# T06_preliminarySchematic_v4.net
KiCad netlist of a schematic drawn in EAGLE
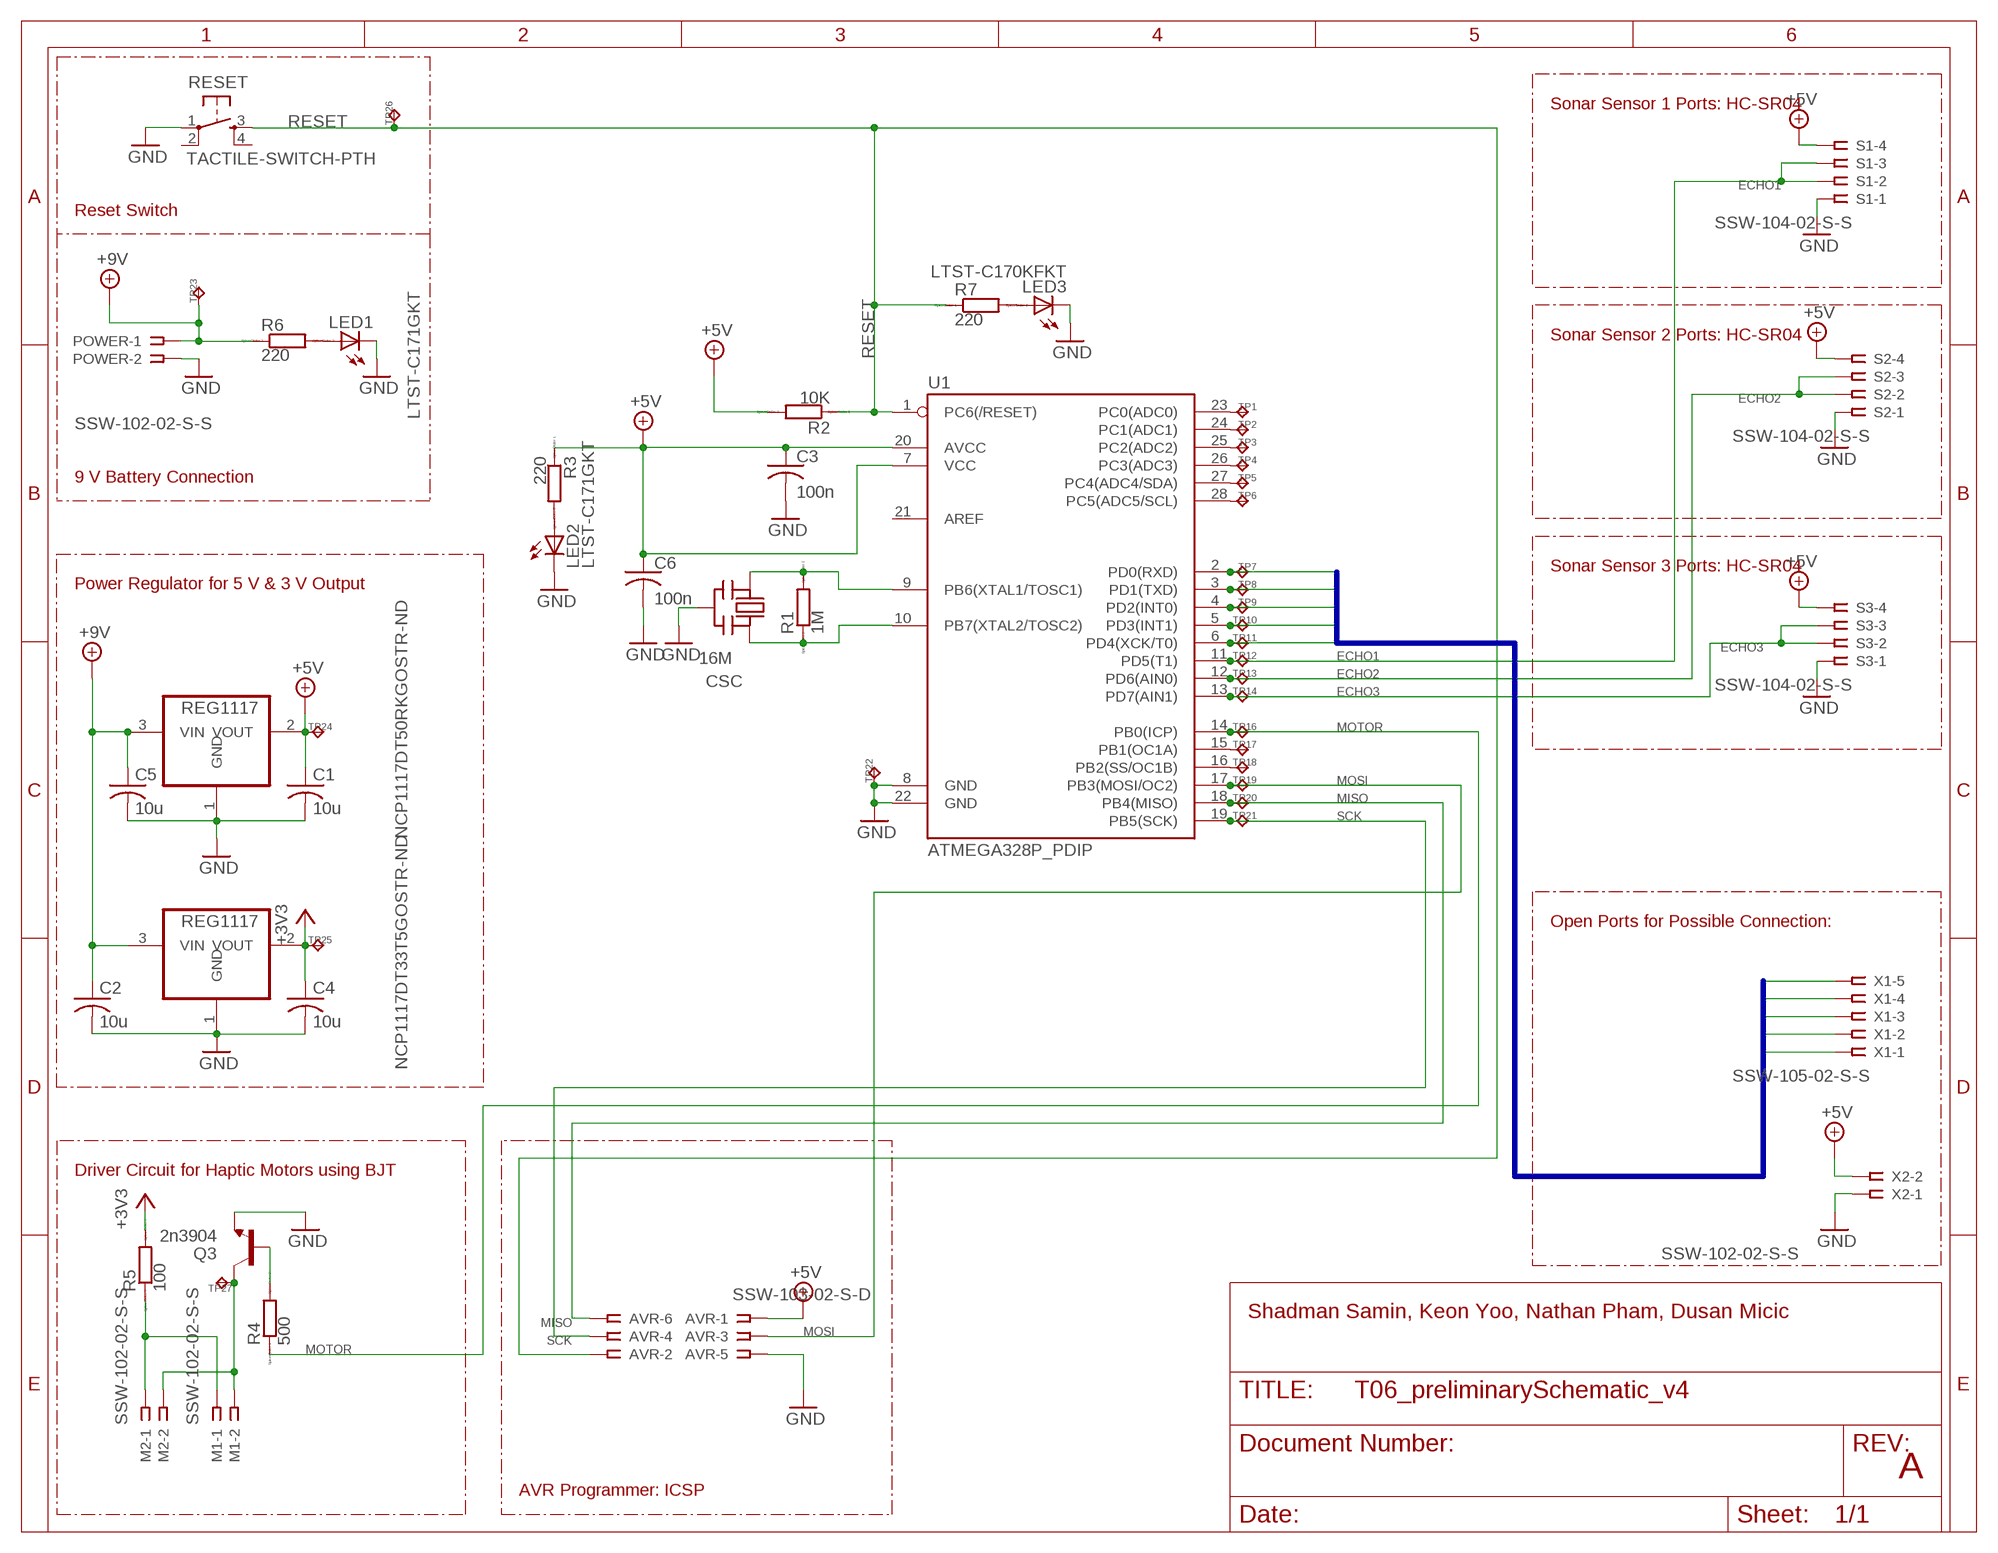
[diagram p0: schematic, sheet 1]

(export (version "E")
  (design (tool "Eeschema 10.0.6"))
  (components
    (comp (ref "AVR")
      (value "SSW-103-02-S-D")
      (footprint "eagle-import:SSW-103-02-S-D")
      (libsource (lib "eagle-import") (part "SSW-103-02-S-D"))
    )
    (comp (ref "C1")
      (value "10u")
      (footprint "eagle-import:C0805K")
      (libsource (lib "eagle-import") (part "C-USC0805K"))
    )
    (comp (ref "C2")
      (value "10u")
      (footprint "eagle-import:C0805K")
      (libsource (lib "eagle-import") (part "C-USC0805K"))
    )
    (comp (ref "C3")
      (value "100n")
      (footprint "eagle-import:C0805K")
      (libsource (lib "eagle-import") (part "rcl_C-USC0805K"))
    )
    (comp (ref "C4")
      (value "10u")
      (footprint "eagle-import:C0805K")
      (libsource (lib "eagle-import") (part "C-USC0805K"))
    )
    (comp (ref "C5")
      (value "10u")
      (footprint "eagle-import:C0805K")
      (libsource (lib "eagle-import") (part "C-USC0805K"))
    )
    (comp (ref "C6")
      (value "100n")
      (footprint "eagle-import:C0805K")
      (libsource (lib "eagle-import") (part "rcl_C-USC0805K"))
    )
    (comp (ref "CSC")
      (value "16M")
      (footprint "eagle-import:CSTCR-G")
      (libsource (lib "eagle-import") (part "CERMOSCILL-CSTCRG"))
    )
    (comp (ref "LED1")
      (value "LTST-C171GKT")
      (footprint "eagle-import:CHIPLED_0805")
      (libsource (lib "eagle-import") (part "LEDCHIPLED_0805"))
    )
    (comp (ref "LED2")
      (value "LTST-C171GKT")
      (footprint "eagle-import:CHIP-LED0805")
      (libsource (lib "eagle-import") (part "LEDCHIP-LED0805"))
    )
    (comp (ref "LED3")
      (value "LTST-C170KFKT")
      (footprint "eagle-import:CHIP-LED0805")
      (libsource (lib "eagle-import") (part "LEDCHIP-LED0805"))
    )
    (comp (ref "M1")
      (value "SSW-102-02-S-S")
      (footprint "eagle-import:SSW-102-02-S-S")
      (libsource (lib "eagle-import") (part "SSW-102-02-S-S"))
    )
    (comp (ref "M2")
      (value "SSW-102-02-S-S")
      (footprint "eagle-import:SSW-102-02-S-S")
      (libsource (lib "eagle-import") (part "SSW-102-02-S-S"))
    )
    (comp (ref "NCP1117DT33T5GOSTR-ND")
      (value "REG1117")
      (footprint "eagle-import:SOT223")
      (libsource (lib "eagle-import") (part "REG1117"))
    )
    (comp (ref "NCP1117DT50RKGOSTR-ND")
      (value "REG1117")
      (footprint "eagle-import:SOT223")
      (libsource (lib "eagle-import") (part "REG1117"))
    )
    (comp (ref "POWER")
      (value "SSW-102-02-S-S")
      (footprint "eagle-import:SSW-102-02-S-S")
      (libsource (lib "eagle-import") (part "SSW-102-02-S-S"))
    )
    (comp (ref "Q3")
      (value "2n3904")
      (footprint "eagle-import:TO-92")
      (libsource (lib "eagle-import") (part "TRANSISTOR_NPN2N3904"))
    )
    (comp (ref "R1")
      (value "1M")
      (footprint "eagle-import:R0603")
      (libsource (lib "eagle-import") (part "RR0603"))
    )
    (comp (ref "R2")
      (value "10K")
      (footprint "eagle-import:R0603")
      (libsource (lib "eagle-import") (part "RR0603"))
    )
    (comp (ref "R3")
      (value "220")
      (footprint "eagle-import:R0603")
      (libsource (lib "eagle-import") (part "RR0603"))
    )
    (comp (ref "R4")
      (value "500")
      (footprint "eagle-import:R0603")
      (libsource (lib "eagle-import") (part "RR0603"))
    )
    (comp (ref "R5")
      (value "100")
      (footprint "eagle-import:R0603")
      (libsource (lib "eagle-import") (part "RR0603"))
    )
    (comp (ref "R6")
      (value "220")
      (footprint "eagle-import:R0603")
      (libsource (lib "eagle-import") (part "RR0603"))
    )
    (comp (ref "R7")
      (value "220")
      (footprint "eagle-import:R0603")
      (libsource (lib "eagle-import") (part "RR0603"))
    )
    (comp (ref "RESET")
      (value "TACTILE-SWITCH-PTH")
      (footprint "eagle-import:TAC-SWITCH-PTH")
      (libsource (lib "eagle-import") (part "TACTILE-SWITCH-PTH"))
    )
    (comp (ref "S1")
      (value "SSW-104-02-S-S")
      (footprint "eagle-import:SSW-104-02-S-S")
      (libsource (lib "eagle-import") (part "SSW-104-02-S-S"))
    )
    (comp (ref "S2")
      (value "SSW-104-02-S-S")
      (footprint "eagle-import:SSW-104-02-S-S")
      (libsource (lib "eagle-import") (part "SSW-104-02-S-S"))
    )
    (comp (ref "S3")
      (value "SSW-104-02-S-S")
      (footprint "eagle-import:SSW-104-02-S-S")
      (libsource (lib "eagle-import") (part "SSW-104-02-S-S"))
    )
    (comp (ref "TP1")
      (value "TPPAD1-13")
      (footprint "eagle-import:P1-13")
      (libsource (lib "eagle-import") (part "TPPAD1-13"))
    )
    (comp (ref "TP2")
      (value "TPPAD1-13")
      (footprint "eagle-import:P1-13")
      (libsource (lib "eagle-import") (part "TPPAD1-13"))
    )
    (comp (ref "TP3")
      (value "TPPAD1-13")
      (footprint "eagle-import:P1-13")
      (libsource (lib "eagle-import") (part "TPPAD1-13"))
    )
    (comp (ref "TP4")
      (value "TPPAD1-13")
      (footprint "eagle-import:P1-13")
      (libsource (lib "eagle-import") (part "TPPAD1-13"))
    )
    (comp (ref "TP5")
      (value "TPPAD1-13")
      (footprint "eagle-import:P1-13")
      (libsource (lib "eagle-import") (part "TPPAD1-13"))
    )
    (comp (ref "TP6")
      (value "TPPAD1-13")
      (footprint "eagle-import:P1-13")
      (libsource (lib "eagle-import") (part "TPPAD1-13"))
    )
    (comp (ref "TP7")
      (value "TPPAD1-13")
      (footprint "eagle-import:P1-13")
      (libsource (lib "eagle-import") (part "TPPAD1-13"))
    )
    (comp (ref "TP8")
      (value "TPPAD1-13")
      (footprint "eagle-import:P1-13")
      (libsource (lib "eagle-import") (part "TPPAD1-13"))
    )
    (comp (ref "TP9")
      (value "TPPAD1-13")
      (footprint "eagle-import:P1-13")
      (libsource (lib "eagle-import") (part "TPPAD1-13"))
    )
    (comp (ref "TP10")
      (value "TPPAD1-13")
      (footprint "eagle-import:P1-13")
      (libsource (lib "eagle-import") (part "TPPAD1-13"))
    )
    (comp (ref "TP11")
      (value "TPPAD1-13")
      (footprint "eagle-import:P1-13")
      (libsource (lib "eagle-import") (part "TPPAD1-13"))
    )
    (comp (ref "TP12")
      (value "TPPAD1-13")
      (footprint "eagle-import:P1-13")
      (libsource (lib "eagle-import") (part "TPPAD1-13"))
    )
    (comp (ref "TP13")
      (value "TPPAD1-13")
      (footprint "eagle-import:P1-13")
      (libsource (lib "eagle-import") (part "TPPAD1-13"))
    )
    (comp (ref "TP14")
      (value "TPPAD1-13")
      (footprint "eagle-import:P1-13")
      (libsource (lib "eagle-import") (part "TPPAD1-13"))
    )
    (comp (ref "TP16")
      (value "TPPAD1-13")
      (footprint "eagle-import:P1-13")
      (libsource (lib "eagle-import") (part "TPPAD1-13"))
    )
    (comp (ref "TP17")
      (value "TPPAD1-13")
      (footprint "eagle-import:P1-13")
      (libsource (lib "eagle-import") (part "TPPAD1-13"))
    )
    (comp (ref "TP18")
      (value "TPPAD1-13")
      (footprint "eagle-import:P1-13")
      (libsource (lib "eagle-import") (part "TPPAD1-13"))
    )
    (comp (ref "TP19")
      (value "TPPAD1-13")
      (footprint "eagle-import:P1-13")
      (libsource (lib "eagle-import") (part "TPPAD1-13"))
    )
    (comp (ref "TP20")
      (value "TPPAD1-13")
      (footprint "eagle-import:P1-13")
      (libsource (lib "eagle-import") (part "TPPAD1-13"))
    )
    (comp (ref "TP21")
      (value "TPPAD1-13")
      (footprint "eagle-import:P1-13")
      (libsource (lib "eagle-import") (part "TPPAD1-13"))
    )
    (comp (ref "TP22")
      (value "TPPAD1-13")
      (footprint "eagle-import:P1-13")
      (libsource (lib "eagle-import") (part "TPPAD1-13"))
    )
    (comp (ref "TP23")
      (value "TPPAD1-13")
      (footprint "eagle-import:P1-13")
      (libsource (lib "eagle-import") (part "TPPAD1-13"))
    )
    (comp (ref "TP24")
      (value "TPPAD1-13")
      (footprint "eagle-import:P1-13")
      (libsource (lib "eagle-import") (part "TPPAD1-13"))
    )
    (comp (ref "TP25")
      (value "TPPAD1-13")
      (footprint "eagle-import:P1-13")
      (libsource (lib "eagle-import") (part "TPPAD1-13"))
    )
    (comp (ref "TP26")
      (value "TPPAD1-13")
      (footprint "eagle-import:P1-13")
      (libsource (lib "eagle-import") (part "TPPAD1-13"))
    )
    (comp (ref "TP27")
      (value "TPPAD1-13")
      (footprint "eagle-import:P1-13")
      (libsource (lib "eagle-import") (part "TPPAD1-13"))
    )
    (comp (ref "U1")
      (value "ATMEGA328P_PDIP")
      (footprint "eagle-import:DIL28-3")
      (libsource (lib "eagle-import") (part "ATMEGA328P_PDIP"))
    )
    (comp (ref "X1")
      (value "SSW-105-02-S-S")
      (footprint "eagle-import:SSW-105-02-S-S")
      (libsource (lib "eagle-import") (part "SSW-105-02-S-S"))
    )
    (comp (ref "X2")
      (value "SSW-102-02-S-S")
      (footprint "eagle-import:SSW-102-02-S-S")
      (libsource (lib "eagle-import") (part "SSW-102-02-S-S"))
    )
  )
  (nets
    (net (code "1") (name "+3V3") (class "Default")
      (node (ref "C4") (pin "1") (pinfunction "1_1") (pintype "passive"))
      (node (ref "NCP1117DT33T5GOSTR-ND") (pin "2") (pinfunction "VOUT_2") (pintype "output"))
      (node (ref "R5") (pin "2") (pinfunction "2_2") (pintype "passive"))
      (node (ref "TP25") (pin "TP") (pinfunction "TP_TP") (pintype "input"))
    )
    (net (code "2") (name "+5V") (class "Default")
      (node (ref "AVR") (pin "1") (pinfunction "1_1") (pintype "passive"))
      (node (ref "C1") (pin "1") (pinfunction "1_1") (pintype "passive"))
      (node (ref "C3") (pin "1") (pinfunction "1_1") (pintype "passive"))
      (node (ref "C6") (pin "1") (pinfunction "1_1") (pintype "passive"))
      (node (ref "NCP1117DT50RKGOSTR-ND") (pin "2") (pinfunction "VOUT_2") (pintype "output"))
      (node (ref "R2") (pin "2") (pinfunction "2_2") (pintype "passive"))
      (node (ref "R3") (pin "1") (pinfunction "1_1") (pintype "passive"))
      (node (ref "S1") (pin "4") (pinfunction "1_4") (pintype "passive"))
      (node (ref "S2") (pin "4") (pinfunction "1_4") (pintype "passive"))
      (node (ref "S3") (pin "4") (pinfunction "1_4") (pintype "passive"))
      (node (ref "TP24") (pin "TP") (pinfunction "TP_TP") (pintype "input"))
      (node (ref "U1") (pin "20") (pinfunction "AVCC_20") (pintype "bidirectional"))
      (node (ref "U1") (pin "7") (pinfunction "VCC_7") (pintype "bidirectional"))
      (node (ref "X2") (pin "2") (pinfunction "1_2") (pintype "passive"))
    )
    (net (code "3") (name "+9V") (class "Default")
      (node (ref "C2") (pin "1") (pinfunction "1_1") (pintype "passive"))
      (node (ref "C5") (pin "1") (pinfunction "1_1") (pintype "passive"))
      (node (ref "NCP1117DT33T5GOSTR-ND") (pin "3") (pinfunction "VIN_3") (pintype "input"))
      (node (ref "NCP1117DT50RKGOSTR-ND") (pin "3") (pinfunction "VIN_3") (pintype "input"))
      (node (ref "POWER") (pin "1") (pinfunction "1_1") (pintype "passive"))
      (node (ref "R6") (pin "1") (pinfunction "1_1") (pintype "passive"))
      (node (ref "TP23") (pin "TP") (pinfunction "TP_TP") (pintype "input"))
    )
    (net (code "4") (name "/BU0") (class "Default")
      (node (ref "TP7") (pin "TP") (pinfunction "TP_TP") (pintype "input"))
      (node (ref "U1") (pin "2") (pinfunction "PD0(RXD)_2") (pintype "bidirectional"))
      (node (ref "X1") (pin "1") (pinfunction "1_1") (pintype "passive"))
    )
    (net (code "5") (name "/BU1") (class "Default")
      (node (ref "TP8") (pin "TP") (pinfunction "TP_TP") (pintype "input"))
      (node (ref "U1") (pin "3") (pinfunction "PD1(TXD)_3") (pintype "bidirectional"))
      (node (ref "X1") (pin "2") (pinfunction "1_2") (pintype "passive"))
    )
    (net (code "6") (name "/BU2") (class "Default")
      (node (ref "TP9") (pin "TP") (pinfunction "TP_TP") (pintype "input"))
      (node (ref "U1") (pin "4") (pinfunction "PD2(INT0)_4") (pintype "bidirectional"))
      (node (ref "X1") (pin "3") (pinfunction "1_3") (pintype "passive"))
    )
    (net (code "7") (name "/BU3") (class "Default")
      (node (ref "TP10") (pin "TP") (pinfunction "TP_TP") (pintype "input"))
      (node (ref "U1") (pin "5") (pinfunction "PD3(INT1)_5") (pintype "bidirectional"))
      (node (ref "X1") (pin "4") (pinfunction "1_4") (pintype "passive"))
    )
    (net (code "8") (name "/BU4") (class "Default")
      (node (ref "TP11") (pin "TP") (pinfunction "TP_TP") (pintype "input"))
      (node (ref "U1") (pin "6") (pinfunction "PD4(XCK/T0)_6") (pintype "bidirectional"))
      (node (ref "X1") (pin "5") (pinfunction "1_5") (pintype "passive"))
    )
    (net (code "9") (name "/ECHO1") (class "Default")
      (node (ref "S1") (pin "2") (pinfunction "1_2") (pintype "passive"))
      (node (ref "S1") (pin "3") (pinfunction "1_3") (pintype "passive"))
      (node (ref "TP12") (pin "TP") (pinfunction "TP_TP") (pintype "input"))
      (node (ref "U1") (pin "11") (pinfunction "PD5(T1)_11") (pintype "bidirectional"))
    )
    (net (code "10") (name "/ECHO2") (class "Default")
      (node (ref "S2") (pin "2") (pinfunction "1_2") (pintype "passive"))
      (node (ref "S2") (pin "3") (pinfunction "1_3") (pintype "passive"))
      (node (ref "TP13") (pin "TP") (pinfunction "TP_TP") (pintype "input"))
      (node (ref "U1") (pin "12") (pinfunction "PD6(AIN0)_12") (pintype "bidirectional"))
    )
    (net (code "11") (name "/ECHO3") (class "Default")
      (node (ref "S3") (pin "2") (pinfunction "1_2") (pintype "passive"))
      (node (ref "S3") (pin "3") (pinfunction "1_3") (pintype "passive"))
      (node (ref "TP14") (pin "TP") (pinfunction "TP_TP") (pintype "input"))
      (node (ref "U1") (pin "13") (pinfunction "PD7(AIN1)_13") (pintype "bidirectional"))
    )
    (net (code "12") (name "/MISO") (class "Default")
      (node (ref "AVR") (pin "6") (pinfunction "1_6") (pintype "passive"))
      (node (ref "TP20") (pin "TP") (pinfunction "TP_TP") (pintype "input"))
      (node (ref "U1") (pin "18") (pinfunction "PB4(MISO)_18") (pintype "bidirectional"))
    )
    (net (code "13") (name "/MOSI") (class "Default")
      (node (ref "AVR") (pin "3") (pinfunction "1_3") (pintype "passive"))
      (node (ref "TP19") (pin "TP") (pinfunction "TP_TP") (pintype "input"))
      (node (ref "U1") (pin "17") (pinfunction "PB3(MOSI/OC2)_17") (pintype "bidirectional"))
    )
    (net (code "14") (name "/MOTOR") (class "Default")
      (node (ref "R4") (pin "1") (pinfunction "1_1") (pintype "passive"))
      (node (ref "TP16") (pin "TP") (pinfunction "TP_TP") (pintype "input"))
      (node (ref "U1") (pin "14") (pinfunction "PB0(ICP)_14") (pintype "bidirectional"))
    )
    (net (code "15") (name "/RESET") (class "Default")
      (node (ref "AVR") (pin "2") (pinfunction "1_2") (pintype "passive"))
      (node (ref "R2") (pin "1") (pinfunction "1_1") (pintype "passive"))
      (node (ref "R7") (pin "1") (pinfunction "1_1") (pintype "passive"))
      (node (ref "RESET") (pin "3") (pinfunction "3_3") (pintype "passive"))
      (node (ref "TP26") (pin "TP") (pinfunction "TP_TP") (pintype "input"))
      (node (ref "U1") (pin "1") (pinfunction "PC6(/RESET)_1") (pintype "bidirectional"))
    )
    (net (code "16") (name "/SCK") (class "Default")
      (node (ref "AVR") (pin "4") (pinfunction "1_4") (pintype "passive"))
      (node (ref "TP21") (pin "TP") (pinfunction "TP_TP") (pintype "input"))
      (node (ref "U1") (pin "19") (pinfunction "PB5(SCK)_19") (pintype "bidirectional"))
    )
    (net (code "17") (name "GND") (class "Default")
      (node (ref "AVR") (pin "5") (pinfunction "1_5") (pintype "passive"))
      (node (ref "C1") (pin "2") (pinfunction "2_2") (pintype "passive"))
      (node (ref "C2") (pin "2") (pinfunction "2_2") (pintype "passive"))
      (node (ref "C3") (pin "2") (pinfunction "2_2") (pintype "passive"))
      (node (ref "C4") (pin "2") (pinfunction "2_2") (pintype "passive"))
      (node (ref "C5") (pin "2") (pinfunction "2_2") (pintype "passive"))
      (node (ref "C6") (pin "2") (pinfunction "2_2") (pintype "passive"))
      (node (ref "CSC") (pin "2") (pinfunction "GND_2") (pintype "bidirectional"))
      (node (ref "LED1") (pin "C") (pinfunction "C_C") (pintype "passive"))
      (node (ref "LED2") (pin "C") (pinfunction "C_C") (pintype "passive"))
      (node (ref "LED3") (pin "C") (pinfunction "C_C") (pintype "passive"))
      (node (ref "NCP1117DT33T5GOSTR-ND") (pin "1") (pinfunction "GND_1") (pintype "power_in"))
      (node (ref "NCP1117DT50RKGOSTR-ND") (pin "1") (pinfunction "GND_1") (pintype "power_in"))
      (node (ref "POWER") (pin "2") (pinfunction "1_2") (pintype "passive"))
      (node (ref "Q3") (pin "1") (pinfunction "E_1") (pintype "passive"))
      (node (ref "RESET") (pin "1") (pinfunction "1_1") (pintype "passive"))
      (node (ref "S1") (pin "1") (pinfunction "1_1") (pintype "passive"))
      (node (ref "S2") (pin "1") (pinfunction "1_1") (pintype "passive"))
      (node (ref "S3") (pin "1") (pinfunction "1_1") (pintype "passive"))
      (node (ref "TP22") (pin "TP") (pinfunction "TP_TP") (pintype "input"))
      (node (ref "U1") (pin "22") (pinfunction "GND_22") (pintype "bidirectional"))
      (node (ref "U1") (pin "8") (pinfunction "GND_8") (pintype "bidirectional"))
      (node (ref "X2") (pin "1") (pinfunction "1_1") (pintype "passive"))
    )
    (net (code "18") (name "Net-(CSC-IN)") (class "Default")
      (node (ref "CSC") (pin "1") (pinfunction "IN_1") (pintype "bidirectional"))
      (node (ref "R1") (pin "2") (pinfunction "2_2") (pintype "passive"))
      (node (ref "U1") (pin "9") (pinfunction "PB6(XTAL1/TOSC1)_9") (pintype "bidirectional"))
    )
    (net (code "19") (name "Net-(CSC-OUT)") (class "Default")
      (node (ref "CSC") (pin "3") (pinfunction "OUT_3") (pintype "bidirectional"))
      (node (ref "R1") (pin "1") (pinfunction "1_1") (pintype "passive"))
      (node (ref "U1") (pin "10") (pinfunction "PB7(XTAL2/TOSC2)_10") (pintype "bidirectional"))
    )
    (net (code "20") (name "Net-(LED1-PadA)") (class "Default")
      (node (ref "LED1") (pin "A") (pinfunction "A_A") (pintype "passive"))
      (node (ref "R6") (pin "2") (pinfunction "2_2") (pintype "passive"))
    )
    (net (code "21") (name "Net-(LED2-PadA)") (class "Default")
      (node (ref "LED2") (pin "A") (pinfunction "A_A") (pintype "passive"))
      (node (ref "R3") (pin "2") (pinfunction "2_2") (pintype "passive"))
    )
    (net (code "22") (name "Net-(LED3-PadA)") (class "Default")
      (node (ref "LED3") (pin "A") (pinfunction "A_A") (pintype "passive"))
      (node (ref "R7") (pin "2") (pinfunction "2_2") (pintype "passive"))
    )
    (net (code "23") (name "Net-(M1-Pad1)") (class "Default")
      (node (ref "M1") (pin "1") (pinfunction "1_1") (pintype "passive"))
      (node (ref "M2") (pin "1") (pinfunction "1_1") (pintype "passive"))
      (node (ref "R5") (pin "1") (pinfunction "1_1") (pintype "passive"))
    )
    (net (code "24") (name "Net-(M1B-1)") (class "Default")
      (node (ref "M1") (pin "2") (pinfunction "1_2") (pintype "passive"))
      (node (ref "M2") (pin "2") (pinfunction "1_2") (pintype "passive"))
      (node (ref "Q3") (pin "3") (pinfunction "C_3") (pintype "passive"))
      (node (ref "TP27") (pin "TP") (pinfunction "TP_TP") (pintype "input"))
    )
    (net (code "25") (name "Net-(Q3-B)") (class "Default")
      (node (ref "Q3") (pin "2") (pinfunction "B_2") (pintype "passive"))
      (node (ref "R4") (pin "2") (pinfunction "2_2") (pintype "passive"))
    )
    (net (code "26") (name "Net-(U1-PB1(OC1A))") (class "Default")
      (node (ref "TP17") (pin "TP") (pinfunction "TP_TP") (pintype "input"))
      (node (ref "U1") (pin "15") (pinfunction "PB1(OC1A)_15") (pintype "bidirectional"))
    )
    (net (code "27") (name "Net-(U1-PB2(SS{slash}OC1B))") (class "Default")
      (node (ref "TP18") (pin "TP") (pinfunction "TP_TP") (pintype "input"))
      (node (ref "U1") (pin "16") (pinfunction "PB2(SS/OC1B)_16") (pintype "bidirectional"))
    )
    (net (code "28") (name "Net-(U1-PC0(ADC0))") (class "Default")
      (node (ref "TP1") (pin "TP") (pinfunction "TP_TP") (pintype "input"))
      (node (ref "U1") (pin "23") (pinfunction "PC0(ADC0)_23") (pintype "bidirectional"))
    )
    (net (code "29") (name "Net-(U1-PC1(ADC1))") (class "Default")
      (node (ref "TP2") (pin "TP") (pinfunction "TP_TP") (pintype "input"))
      (node (ref "U1") (pin "24") (pinfunction "PC1(ADC1)_24") (pintype "bidirectional"))
    )
    (net (code "30") (name "Net-(U1-PC2(ADC2))") (class "Default")
      (node (ref "TP3") (pin "TP") (pinfunction "TP_TP") (pintype "input"))
      (node (ref "U1") (pin "25") (pinfunction "PC2(ADC2)_25") (pintype "bidirectional"))
    )
    (net (code "31") (name "Net-(U1-PC3(ADC3))") (class "Default")
      (node (ref "TP4") (pin "TP") (pinfunction "TP_TP") (pintype "input"))
      (node (ref "U1") (pin "26") (pinfunction "PC3(ADC3)_26") (pintype "bidirectional"))
    )
    (net (code "32") (name "Net-(U1-PC4(ADC4{slash}SDA))") (class "Default")
      (node (ref "TP5") (pin "TP") (pinfunction "TP_TP") (pintype "input"))
      (node (ref "U1") (pin "27") (pinfunction "PC4(ADC4/SDA)_27") (pintype "bidirectional"))
    )
    (net (code "33") (name "Net-(U1-PC5(ADC5{slash}SCL))") (class "Default")
      (node (ref "TP6") (pin "TP") (pinfunction "TP_TP") (pintype "input"))
      (node (ref "U1") (pin "28") (pinfunction "PC5(ADC5/SCL)_28") (pintype "bidirectional"))
    )
    (net (code "34") (name "unconnected-(RESET-Pad2)") (class "Default")
      (node (ref "RESET") (pin "2") (pinfunction "2_2") (pintype "passive"))
    )
    (net (code "35") (name "unconnected-(RESET-Pad4)") (class "Default")
      (node (ref "RESET") (pin "4") (pinfunction "4_4") (pintype "passive"))
    )
    (net (code "36") (name "unconnected-(U1-AREF-Pad21)") (class "Default")
      (node (ref "U1") (pin "21") (pinfunction "AREF_21") (pintype "bidirectional"))
    )
  )
)
